# Brava_Monio.net
KiCad netlist of a schematic drawn in EAGLE
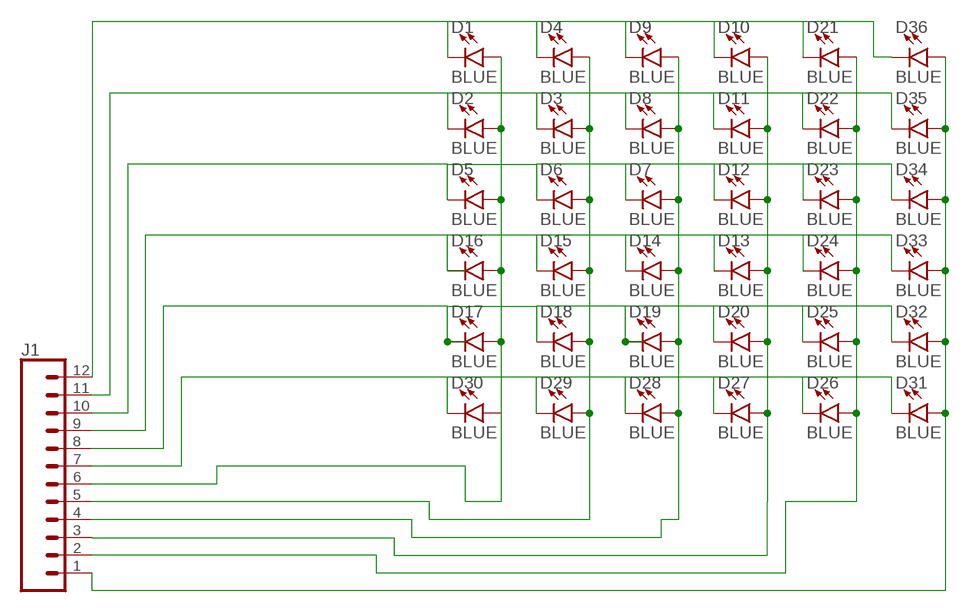
[diagram p0: schematic, sheet 1]

(export (version "E")
  (design (tool "Eeschema 10.0.6"))
  (components
    (comp (ref "D1")
      (value "BLUE")
      (footprint "eagle-import:LED-0603")
      (libsource (lib "eagle-import") (part "LED-BLUE0603"))
    )
    (comp (ref "D2")
      (value "BLUE")
      (footprint "eagle-import:LED-0603")
      (libsource (lib "eagle-import") (part "LED-BLUE0603"))
    )
    (comp (ref "D3")
      (value "BLUE")
      (footprint "eagle-import:LED-0603")
      (libsource (lib "eagle-import") (part "LED-BLUE0603"))
    )
    (comp (ref "D4")
      (value "BLUE")
      (footprint "eagle-import:LED-0603")
      (libsource (lib "eagle-import") (part "LED-BLUE0603"))
    )
    (comp (ref "D5")
      (value "BLUE")
      (footprint "eagle-import:LED-0603")
      (libsource (lib "eagle-import") (part "LED-BLUE0603"))
    )
    (comp (ref "D6")
      (value "BLUE")
      (footprint "eagle-import:LED-0603")
      (libsource (lib "eagle-import") (part "LED-BLUE0603"))
    )
    (comp (ref "D7")
      (value "BLUE")
      (footprint "eagle-import:LED-0603")
      (libsource (lib "eagle-import") (part "LED-BLUE0603"))
    )
    (comp (ref "D8")
      (value "BLUE")
      (footprint "eagle-import:LED-0603")
      (libsource (lib "eagle-import") (part "LED-BLUE0603"))
    )
    (comp (ref "D9")
      (value "BLUE")
      (footprint "eagle-import:LED-0603")
      (libsource (lib "eagle-import") (part "LED-BLUE0603"))
    )
    (comp (ref "D10")
      (value "BLUE")
      (footprint "eagle-import:LED-0603")
      (libsource (lib "eagle-import") (part "LED-BLUE0603"))
    )
    (comp (ref "D11")
      (value "BLUE")
      (footprint "eagle-import:LED-0603")
      (libsource (lib "eagle-import") (part "LED-BLUE0603"))
    )
    (comp (ref "D12")
      (value "BLUE")
      (footprint "eagle-import:LED-0603")
      (libsource (lib "eagle-import") (part "LED-BLUE0603"))
    )
    (comp (ref "D13")
      (value "BLUE")
      (footprint "eagle-import:LED-0603")
      (libsource (lib "eagle-import") (part "LED-BLUE0603"))
    )
    (comp (ref "D14")
      (value "BLUE")
      (footprint "eagle-import:LED-0603")
      (libsource (lib "eagle-import") (part "LED-BLUE0603"))
    )
    (comp (ref "D15")
      (value "BLUE")
      (footprint "eagle-import:LED-0603")
      (libsource (lib "eagle-import") (part "LED-BLUE0603"))
    )
    (comp (ref "D16")
      (value "BLUE")
      (footprint "eagle-import:LED-0603")
      (libsource (lib "eagle-import") (part "LED-BLUE0603"))
    )
    (comp (ref "D17")
      (value "BLUE")
      (footprint "eagle-import:LED-0603")
      (libsource (lib "eagle-import") (part "LED-BLUE0603"))
    )
    (comp (ref "D18")
      (value "BLUE")
      (footprint "eagle-import:LED-0603")
      (libsource (lib "eagle-import") (part "LED-BLUE0603"))
    )
    (comp (ref "D19")
      (value "BLUE")
      (footprint "eagle-import:LED-0603")
      (libsource (lib "eagle-import") (part "LED-BLUE0603"))
    )
    (comp (ref "D20")
      (value "BLUE")
      (footprint "eagle-import:LED-0603")
      (libsource (lib "eagle-import") (part "LED-BLUE0603"))
    )
    (comp (ref "D21")
      (value "BLUE")
      (footprint "eagle-import:LED-0603")
      (libsource (lib "eagle-import") (part "LED-BLUE0603"))
    )
    (comp (ref "D22")
      (value "BLUE")
      (footprint "eagle-import:LED-0603")
      (libsource (lib "eagle-import") (part "LED-BLUE0603"))
    )
    (comp (ref "D23")
      (value "BLUE")
      (footprint "eagle-import:LED-0603")
      (libsource (lib "eagle-import") (part "LED-BLUE0603"))
    )
    (comp (ref "D24")
      (value "BLUE")
      (footprint "eagle-import:LED-0603")
      (libsource (lib "eagle-import") (part "LED-BLUE0603"))
    )
    (comp (ref "D25")
      (value "BLUE")
      (footprint "eagle-import:LED-0603")
      (libsource (lib "eagle-import") (part "LED-BLUE0603"))
    )
    (comp (ref "D26")
      (value "BLUE")
      (footprint "eagle-import:LED-0603")
      (libsource (lib "eagle-import") (part "LED-BLUE0603"))
    )
    (comp (ref "D27")
      (value "BLUE")
      (footprint "eagle-import:LED-0603")
      (libsource (lib "eagle-import") (part "LED-BLUE0603"))
    )
    (comp (ref "D28")
      (value "BLUE")
      (footprint "eagle-import:LED-0603")
      (libsource (lib "eagle-import") (part "LED-BLUE0603"))
    )
    (comp (ref "D29")
      (value "BLUE")
      (footprint "eagle-import:LED-0603")
      (libsource (lib "eagle-import") (part "LED-BLUE0603"))
    )
    (comp (ref "D30")
      (value "BLUE")
      (footprint "eagle-import:LED-0603")
      (libsource (lib "eagle-import") (part "LED-BLUE0603"))
    )
    (comp (ref "D31")
      (value "BLUE")
      (footprint "eagle-import:LED-0603")
      (libsource (lib "eagle-import") (part "LED-BLUE0603"))
    )
    (comp (ref "D32")
      (value "BLUE")
      (footprint "eagle-import:LED-0603")
      (libsource (lib "eagle-import") (part "LED-BLUE0603"))
    )
    (comp (ref "D33")
      (value "BLUE")
      (footprint "eagle-import:LED-0603")
      (libsource (lib "eagle-import") (part "LED-BLUE0603"))
    )
    (comp (ref "D34")
      (value "BLUE")
      (footprint "eagle-import:LED-0603")
      (libsource (lib "eagle-import") (part "LED-BLUE0603"))
    )
    (comp (ref "D35")
      (value "BLUE")
      (footprint "eagle-import:LED-0603")
      (libsource (lib "eagle-import") (part "LED-BLUE0603"))
    )
    (comp (ref "D36")
      (value "BLUE")
      (footprint "eagle-import:LED-0603")
      (libsource (lib "eagle-import") (part "LED-BLUE0603"))
    )
    (comp (ref "J1")
      (value "CONN_12LONGPADS")
      (footprint "eagle-import:1X12_LONGPADS")
      (libsource (lib "eagle-import") (part "CONN_12LONGPADS"))
    )
  )
  (nets
    (net (code "1") (name "Net-(D1-PadA)") (class "Default")
      (node (ref "D1") (pin "A") (pinfunction "A_A") (pintype "passive"))
      (node (ref "D16") (pin "A") (pinfunction "A_A") (pintype "passive"))
      (node (ref "D17") (pin "A") (pinfunction "A_A") (pintype "passive"))
      (node (ref "D2") (pin "A") (pinfunction "A_A") (pintype "passive"))
      (node (ref "D30") (pin "A") (pinfunction "A_A") (pintype "passive"))
      (node (ref "D5") (pin "A") (pinfunction "A_A") (pintype "passive"))
      (node (ref "J1") (pin "6") (pinfunction "6_6") (pintype "passive"))
    )
    (net (code "2") (name "Net-(D1-PadC)") (class "Default")
      (node (ref "D1") (pin "C") (pinfunction "C_C") (pintype "passive"))
      (node (ref "D10") (pin "C") (pinfunction "C_C") (pintype "passive"))
      (node (ref "D21") (pin "C") (pinfunction "C_C") (pintype "passive"))
      (node (ref "D36") (pin "C") (pinfunction "C_C") (pintype "passive"))
      (node (ref "D4") (pin "C") (pinfunction "C_C") (pintype "passive"))
      (node (ref "D9") (pin "C") (pinfunction "C_C") (pintype "passive"))
      (node (ref "J1") (pin "12") (pinfunction "12_12") (pintype "passive"))
    )
    (net (code "3") (name "Net-(D10-PadA)") (class "Default")
      (node (ref "D10") (pin "A") (pinfunction "A_A") (pintype "passive"))
      (node (ref "D11") (pin "A") (pinfunction "A_A") (pintype "passive"))
      (node (ref "D12") (pin "A") (pinfunction "A_A") (pintype "passive"))
      (node (ref "D13") (pin "A") (pinfunction "A_A") (pintype "passive"))
      (node (ref "D20") (pin "A") (pinfunction "A_A") (pintype "passive"))
      (node (ref "D27") (pin "A") (pinfunction "A_A") (pintype "passive"))
      (node (ref "J1") (pin "3") (pinfunction "3_3") (pintype "passive"))
    )
    (net (code "4") (name "Net-(D11-PadC)") (class "Default")
      (node (ref "D11") (pin "C") (pinfunction "C_C") (pintype "passive"))
      (node (ref "D2") (pin "C") (pinfunction "C_C") (pintype "passive"))
      (node (ref "D22") (pin "C") (pinfunction "C_C") (pintype "passive"))
      (node (ref "D3") (pin "C") (pinfunction "C_C") (pintype "passive"))
      (node (ref "D35") (pin "C") (pinfunction "C_C") (pintype "passive"))
      (node (ref "D8") (pin "C") (pinfunction "C_C") (pintype "passive"))
      (node (ref "J1") (pin "11") (pinfunction "11_11") (pintype "passive"))
    )
    (net (code "5") (name "Net-(D12-PadC)") (class "Default")
      (node (ref "D12") (pin "C") (pinfunction "C_C") (pintype "passive"))
      (node (ref "D23") (pin "C") (pinfunction "C_C") (pintype "passive"))
      (node (ref "D34") (pin "C") (pinfunction "C_C") (pintype "passive"))
      (node (ref "D5") (pin "C") (pinfunction "C_C") (pintype "passive"))
      (node (ref "D6") (pin "C") (pinfunction "C_C") (pintype "passive"))
      (node (ref "D7") (pin "C") (pinfunction "C_C") (pintype "passive"))
      (node (ref "J1") (pin "10") (pinfunction "10_10") (pintype "passive"))
    )
    (net (code "6") (name "Net-(D13-PadC)") (class "Default")
      (node (ref "D13") (pin "C") (pinfunction "C_C") (pintype "passive"))
      (node (ref "D14") (pin "C") (pinfunction "C_C") (pintype "passive"))
      (node (ref "D15") (pin "C") (pinfunction "C_C") (pintype "passive"))
      (node (ref "D16") (pin "C") (pinfunction "C_C") (pintype "passive"))
      (node (ref "D24") (pin "C") (pinfunction "C_C") (pintype "passive"))
      (node (ref "D33") (pin "C") (pinfunction "C_C") (pintype "passive"))
      (node (ref "J1") (pin "9") (pinfunction "9_9") (pintype "passive"))
    )
    (net (code "7") (name "Net-(D14-PadA)") (class "Default")
      (node (ref "D14") (pin "A") (pinfunction "A_A") (pintype "passive"))
      (node (ref "D19") (pin "A") (pinfunction "A_A") (pintype "passive"))
      (node (ref "D28") (pin "A") (pinfunction "A_A") (pintype "passive"))
      (node (ref "D7") (pin "A") (pinfunction "A_A") (pintype "passive"))
      (node (ref "D8") (pin "A") (pinfunction "A_A") (pintype "passive"))
      (node (ref "D9") (pin "A") (pinfunction "A_A") (pintype "passive"))
      (node (ref "J1") (pin "4") (pinfunction "4_4") (pintype "passive"))
    )
    (net (code "8") (name "Net-(D15-PadA)") (class "Default")
      (node (ref "D15") (pin "A") (pinfunction "A_A") (pintype "passive"))
      (node (ref "D18") (pin "A") (pinfunction "A_A") (pintype "passive"))
      (node (ref "D29") (pin "A") (pinfunction "A_A") (pintype "passive"))
      (node (ref "D3") (pin "A") (pinfunction "A_A") (pintype "passive"))
      (node (ref "D4") (pin "A") (pinfunction "A_A") (pintype "passive"))
      (node (ref "D6") (pin "A") (pinfunction "A_A") (pintype "passive"))
      (node (ref "J1") (pin "5") (pinfunction "5_5") (pintype "passive"))
    )
    (net (code "9") (name "Net-(D17-PadC)") (class "Default")
      (node (ref "D17") (pin "C") (pinfunction "C_C") (pintype "passive"))
      (node (ref "D18") (pin "C") (pinfunction "C_C") (pintype "passive"))
      (node (ref "D19") (pin "C") (pinfunction "C_C") (pintype "passive"))
      (node (ref "D20") (pin "C") (pinfunction "C_C") (pintype "passive"))
      (node (ref "D25") (pin "C") (pinfunction "C_C") (pintype "passive"))
      (node (ref "D32") (pin "C") (pinfunction "C_C") (pintype "passive"))
      (node (ref "J1") (pin "8") (pinfunction "8_8") (pintype "passive"))
    )
    (net (code "10") (name "Net-(D21-PadA)") (class "Default")
      (node (ref "D21") (pin "A") (pinfunction "A_A") (pintype "passive"))
      (node (ref "D22") (pin "A") (pinfunction "A_A") (pintype "passive"))
      (node (ref "D23") (pin "A") (pinfunction "A_A") (pintype "passive"))
      (node (ref "D24") (pin "A") (pinfunction "A_A") (pintype "passive"))
      (node (ref "D25") (pin "A") (pinfunction "A_A") (pintype "passive"))
      (node (ref "D26") (pin "A") (pinfunction "A_A") (pintype "passive"))
      (node (ref "J1") (pin "2") (pinfunction "2_2") (pintype "passive"))
    )
    (net (code "11") (name "Net-(D26-PadC)") (class "Default")
      (node (ref "D26") (pin "C") (pinfunction "C_C") (pintype "passive"))
      (node (ref "D27") (pin "C") (pinfunction "C_C") (pintype "passive"))
      (node (ref "D28") (pin "C") (pinfunction "C_C") (pintype "passive"))
      (node (ref "D29") (pin "C") (pinfunction "C_C") (pintype "passive"))
      (node (ref "D30") (pin "C") (pinfunction "C_C") (pintype "passive"))
      (node (ref "D31") (pin "C") (pinfunction "C_C") (pintype "passive"))
      (node (ref "J1") (pin "7") (pinfunction "7_7") (pintype "passive"))
    )
    (net (code "12") (name "Net-(D31-PadA)") (class "Default")
      (node (ref "D31") (pin "A") (pinfunction "A_A") (pintype "passive"))
      (node (ref "D32") (pin "A") (pinfunction "A_A") (pintype "passive"))
      (node (ref "D33") (pin "A") (pinfunction "A_A") (pintype "passive"))
      (node (ref "D34") (pin "A") (pinfunction "A_A") (pintype "passive"))
      (node (ref "D35") (pin "A") (pinfunction "A_A") (pintype "passive"))
      (node (ref "D36") (pin "A") (pinfunction "A_A") (pintype "passive"))
      (node (ref "J1") (pin "1") (pinfunction "1_1") (pintype "passive"))
    )
  )
)
